# Bluetooth.net
KiCad netlist of a schematic drawn in Altium Designer
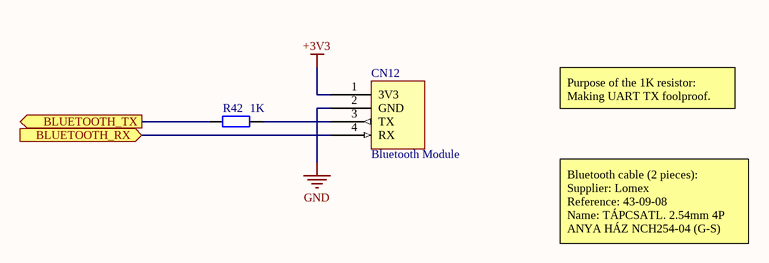
[diagram p0: Bluetooth.SchDoc]

(export (version "E")
  (design (tool "Eeschema 10.0.6"))
  (components
    (comp (ref "CN12")
      (value "Bluetooth Module")
      (footprint "FP_CONN4_TAP_254MM")
      (description "HC-05 tokozva, kérdés, hogy melyik lábon vannak valójában a dolgok")
      (libsource (lib "LKBulls2023") (part "Connector_HC-05"))
    )
    (comp (ref "R42")
      (value "1K")
      (footprint "FP_0805_RES")
      (description "Resistor")
      (fields (field (name "TOLERANCE") "5%") (field (name "POWER") "0.125W"))
      (libsource (lib "LKBulls2023") (part "RES"))
    )
  )
  (nets
    (net (code "1") (name "+3V3") (class "Default")
      (node (ref "CN12") (pin "1") (pinfunction "3V3_1") (pintype "power_in"))
    )
    (net (code "2") (name "/BLUETOOTH_RX") (class "Default")
      (node (ref "CN12") (pin "4") (pinfunction "RX_4") (pintype "input"))
    )
    (net (code "3") (name "/BLUETOOTH_TX") (class "Default")
      (node (ref "R42") (pin "1") (pinfunction "1_1") (pintype "passive"))
    )
    (net (code "4") (name "GND") (class "Default")
      (node (ref "CN12") (pin "2") (pinfunction "GND_2") (pintype "power_in"))
    )
    (net (code "5") (name "Net-(CN12-TX)") (class "Default")
      (node (ref "CN12") (pin "3") (pinfunction "TX_3") (pintype "output"))
      (node (ref "R42") (pin "2") (pinfunction "2_2") (pintype "passive"))
    )
  )
)
